# Back-end.net
KiCad netlist of a schematic drawn in Altium Designer
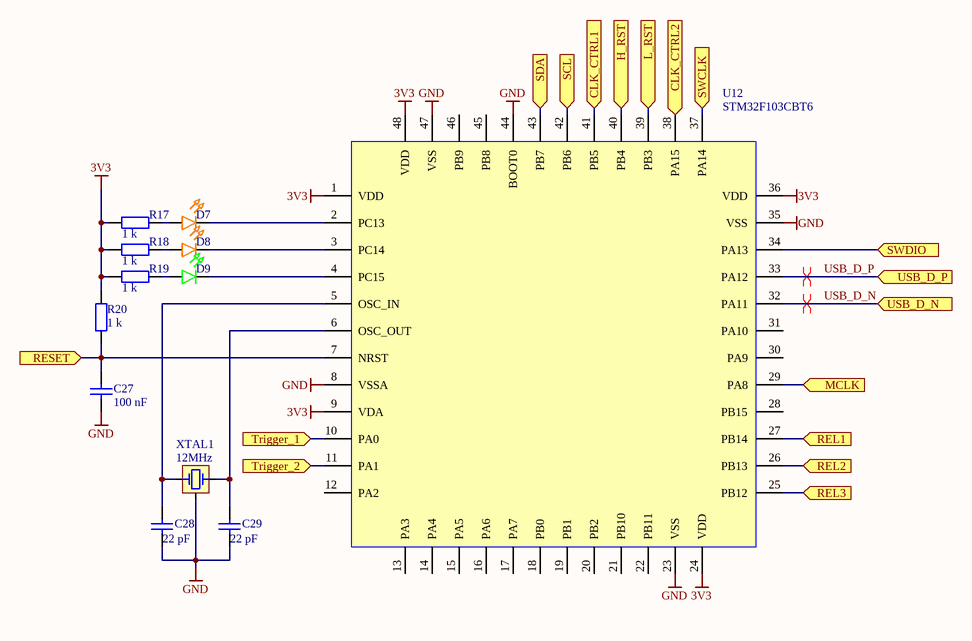
[diagram p0: Back-end.SchDoc]

(export (version "E")
  (design (tool "Eeschema 10.0.6"))
  (components
    (comp (ref "C27")
      (value "100 nF")
      (footprint "C1206")
      (description "Capacitor (Semiconductor SIM Model)")
      (fields (field (name "PUBLISHER") "Altium Limited"))
      (libsource (lib "Miscellaneous Devices") (part "Cap Semi"))
    )
    (comp (ref "C28")
      (value "22 pF")
      (footprint "C1206")
      (description "Capacitor (Semiconductor SIM Model)")
      (fields (field (name "PUBLISHER") "Altium Limited"))
      (libsource (lib "Miscellaneous Devices") (part "Cap Semi"))
    )
    (comp (ref "C29")
      (value "22 pF")
      (footprint "C1206")
      (description "Capacitor (Semiconductor SIM Model)")
      (fields (field (name "PUBLISHER") "Altium Limited"))
      (libsource (lib "Miscellaneous Devices") (part "Cap Semi"))
    )
    (comp (ref "D7")
      (value "LED Orange")
      (footprint "LED Diod red")
      (description "LED SMD Diod Orange")
      (libsource (lib "Diody") (part "LED SMD Diod Orange"))
    )
    (comp (ref "D8")
      (value "LED Orange")
      (footprint "LED Diod red")
      (description "LED SMD Diod Orange")
      (libsource (lib "Diody") (part "LED SMD Diod Orange"))
    )
    (comp (ref "D9")
      (value "*")
      (footprint "LED Diod grean")
      (libsource (lib "Diody") (part "LED SMD Diod Green"))
    )
    (comp (ref "R17")
      (value "1 k")
      (footprint "R1206")
      (description "Resistor")
      (fields (field (name "PUBLISHER") "Altium Limited"))
      (libsource (lib "Miscellaneous Devices") (part "Res2"))
    )
    (comp (ref "R18")
      (value "1 k")
      (footprint "R1206")
      (description "Resistor")
      (fields (field (name "PUBLISHER") "Altium Limited"))
      (libsource (lib "Miscellaneous Devices") (part "Res2"))
    )
    (comp (ref "R19")
      (value "1 k")
      (footprint "R1206")
      (description "Resistor")
      (fields (field (name "PUBLISHER") "Altium Limited"))
      (libsource (lib "Miscellaneous Devices") (part "Res2"))
    )
    (comp (ref "R20")
      (value "1 k")
      (footprint "R1206")
      (description "Resistor")
      (fields (field (name "PUBLISHER") "Altium Limited"))
      (libsource (lib "") (part "Res2_1"))
    )
    (comp (ref "U12")
      (value "STM32F103CBT6")
      (footprint "LQFP48_L")
      (libsource (lib "Schlib1") (part "STM32F070CxTxx"))
    )
    (comp (ref "XTAL1")
      (value "7M-12.000MAAJ-T")
      (footprint "XTAL 2.5MM X3.2MM")
      (description "TXC  7M-12.000MAAJ-T  CRYSTAL, 12MHZ, 18PF, 3.2 X 2.5MM")
      (fields (field (name "VALUE1") "12MHz"))
      (libsource (lib "Passive Components") (part "XTAL 12MHz"))
    )
  )
  (nets
    (net (code "1") (name "/CLK_CTRL1") (class "Default")
      (node (ref "U12") (pin "41") (pinfunction "PB5_41") (pintype "passive"))
    )
    (net (code "2") (name "/CLK_CTRL2") (class "Default")
      (node (ref "U12") (pin "38") (pinfunction "PA15_38") (pintype "passive"))
    )
    (net (code "3") (name "/H_RST") (class "Default")
      (node (ref "U12") (pin "40") (pinfunction "PB4_40") (pintype "passive"))
    )
    (net (code "4") (name "/L_RST") (class "Default")
      (node (ref "U12") (pin "39") (pinfunction "PB3_39") (pintype "passive"))
    )
    (net (code "5") (name "/MCLK") (class "Default")
      (node (ref "U12") (pin "29") (pinfunction "PA8_29") (pintype "passive"))
    )
    (net (code "6") (name "/REL1") (class "Default")
      (node (ref "U12") (pin "27") (pinfunction "PB14_27") (pintype "passive"))
    )
    (net (code "7") (name "/REL2") (class "Default")
      (node (ref "U12") (pin "26") (pinfunction "PB13_26") (pintype "passive"))
    )
    (net (code "8") (name "/REL3") (class "Default")
      (node (ref "U12") (pin "25") (pinfunction "PB12_25") (pintype "passive"))
    )
    (net (code "9") (name "/RESET") (class "Default")
      (node (ref "C27") (pin "2") (pinfunction "2_2") (pintype "passive"))
      (node (ref "R20") (pin "1") (pinfunction "1_1") (pintype "passive"))
      (node (ref "U12") (pin "7") (pinfunction "NRST_7") (pintype "passive"))
    )
    (net (code "10") (name "/SCL") (class "Default")
      (node (ref "U12") (pin "42") (pinfunction "PB6_42") (pintype "passive"))
    )
    (net (code "11") (name "/SDA") (class "Default")
      (node (ref "U12") (pin "43") (pinfunction "PB7_43") (pintype "passive"))
    )
    (net (code "12") (name "/SWCLK") (class "Default")
      (node (ref "U12") (pin "37") (pinfunction "PA14_37") (pintype "passive"))
    )
    (net (code "13") (name "/SWDIO") (class "Default")
      (node (ref "U12") (pin "34") (pinfunction "PA13_34") (pintype "passive"))
    )
    (net (code "14") (name "/Trigger_1") (class "Default")
      (node (ref "U12") (pin "10") (pinfunction "PA0_10") (pintype "passive"))
    )
    (net (code "15") (name "/Trigger_2") (class "Default")
      (node (ref "U12") (pin "11") (pinfunction "PA1_11") (pintype "passive"))
    )
    (net (code "16") (name "/USB_D_N") (class "Default")
      (node (ref "U12") (pin "32") (pinfunction "PA11_32") (pintype "passive"))
    )
    (net (code "17") (name "/USB_D_P") (class "Default")
      (node (ref "U12") (pin "33") (pinfunction "PA12_33") (pintype "passive"))
    )
    (net (code "18") (name "3V3") (class "Default")
      (node (ref "R17") (pin "2") (pinfunction "2_2") (pintype "passive"))
      (node (ref "R18") (pin "2") (pinfunction "2_2") (pintype "passive"))
      (node (ref "R19") (pin "2") (pinfunction "2_2") (pintype "passive"))
      (node (ref "R20") (pin "2") (pinfunction "2_2") (pintype "passive"))
      (node (ref "U12") (pin "1") (pinfunction "VDD_1") (pintype "passive"))
      (node (ref "U12") (pin "24") (pinfunction "VDD_24") (pintype "passive"))
      (node (ref "U12") (pin "36") (pinfunction "VDD_36") (pintype "passive"))
      (node (ref "U12") (pin "48") (pinfunction "VDD_48") (pintype "passive"))
      (node (ref "U12") (pin "9") (pinfunction "VDA_9") (pintype "passive"))
    )
    (net (code "19") (name "GND") (class "Default")
      (node (ref "C27") (pin "1") (pinfunction "1_1") (pintype "passive"))
      (node (ref "C28") (pin "2") (pinfunction "2_2") (pintype "passive"))
      (node (ref "C29") (pin "2") (pinfunction "2_2") (pintype "passive"))
      (node (ref "U12") (pin "23") (pinfunction "VSS_23") (pintype "passive"))
      (node (ref "U12") (pin "35") (pinfunction "VSS_35") (pintype "passive"))
      (node (ref "U12") (pin "44") (pinfunction "BOOT0_44") (pintype "passive"))
      (node (ref "U12") (pin "47") (pinfunction "VSS_47") (pintype "passive"))
      (node (ref "U12") (pin "8") (pinfunction "VSSA_8") (pintype "passive"))
      (node (ref "XTAL1") (pin "2") (pinfunction "2_2") (pintype "power_in"))
    )
    (net (code "20") (name "Net-(D7-Pad1)") (class "Default")
      (node (ref "D7") (pin "1") (pinfunction "1_1") (pintype "power_in"))
      (node (ref "R17") (pin "1") (pinfunction "1_1") (pintype "passive"))
    )
    (net (code "21") (name "Net-(D8-Pad1)") (class "Default")
      (node (ref "D8") (pin "1") (pinfunction "1_1") (pintype "power_in"))
      (node (ref "R18") (pin "1") (pinfunction "1_1") (pintype "passive"))
    )
    (net (code "22") (name "Net-(D9-Pad1)") (class "Default")
      (node (ref "D9") (pin "1") (pinfunction "1_1") (pintype "power_in"))
      (node (ref "R19") (pin "1") (pinfunction "1_1") (pintype "passive"))
    )
    (net (code "23") (name "Net-(U12-OSC_IN)") (class "Default")
      (node (ref "C28") (pin "1") (pinfunction "1_1") (pintype "passive"))
      (node (ref "U12") (pin "5") (pinfunction "OSC_IN_5") (pintype "passive"))
      (node (ref "XTAL1") (pin "1") (pinfunction "OSC1_1") (pintype "passive"))
    )
    (net (code "24") (name "Net-(U12-OSC_OUT)") (class "Default")
      (node (ref "C29") (pin "1") (pinfunction "1_1") (pintype "passive"))
      (node (ref "U12") (pin "6") (pinfunction "OSC_OUT_6") (pintype "passive"))
      (node (ref "XTAL1") (pin "3") (pinfunction "OSC2_3") (pintype "passive"))
    )
    (net (code "25") (name "Net-(U12-PC13)") (class "Default")
      (node (ref "D7") (pin "2") (pinfunction "2_2") (pintype "power_in"))
      (node (ref "U12") (pin "2") (pinfunction "PC13_2") (pintype "passive"))
    )
    (net (code "26") (name "Net-(U12-PC14)") (class "Default")
      (node (ref "D8") (pin "2") (pinfunction "2_2") (pintype "power_in"))
      (node (ref "U12") (pin "3") (pinfunction "PC14_3") (pintype "passive"))
    )
    (net (code "27") (name "Net-(U12-PC15)") (class "Default")
      (node (ref "D9") (pin "2") (pinfunction "2_2") (pintype "power_in"))
      (node (ref "U12") (pin "4") (pinfunction "PC15_4") (pintype "passive"))
    )
    (net (code "28") (name "unconnected-(U12-PA2-Pad12)") (class "Default")
      (node (ref "U12") (pin "12") (pinfunction "PA2_12") (pintype "passive"))
    )
    (net (code "29") (name "unconnected-(U12-PA3-Pad13)") (class "Default")
      (node (ref "U12") (pin "13") (pinfunction "PA3_13") (pintype "passive"))
    )
    (net (code "30") (name "unconnected-(U12-PA4-Pad14)") (class "Default")
      (node (ref "U12") (pin "14") (pinfunction "PA4_14") (pintype "passive"))
    )
    (net (code "31") (name "unconnected-(U12-PA5-Pad15)") (class "Default")
      (node (ref "U12") (pin "15") (pinfunction "PA5_15") (pintype "passive"))
    )
    (net (code "32") (name "unconnected-(U12-PA6-Pad16)") (class "Default")
      (node (ref "U12") (pin "16") (pinfunction "PA6_16") (pintype "passive"))
    )
    (net (code "33") (name "unconnected-(U12-PA7-Pad17)") (class "Default")
      (node (ref "U12") (pin "17") (pinfunction "PA7_17") (pintype "passive"))
    )
    (net (code "34") (name "unconnected-(U12-PA9-Pad30)") (class "Default")
      (node (ref "U12") (pin "30") (pinfunction "PA9_30") (pintype "passive"))
    )
    (net (code "35") (name "unconnected-(U12-PA10-Pad31)") (class "Default")
      (node (ref "U12") (pin "31") (pinfunction "PA10_31") (pintype "passive"))
    )
    (net (code "36") (name "unconnected-(U12-PB0-Pad18)") (class "Default")
      (node (ref "U12") (pin "18") (pinfunction "PB0_18") (pintype "passive"))
    )
    (net (code "37") (name "unconnected-(U12-PB1-Pad19)") (class "Default")
      (node (ref "U12") (pin "19") (pinfunction "PB1_19") (pintype "passive"))
    )
    (net (code "38") (name "unconnected-(U12-PB2-Pad20)") (class "Default")
      (node (ref "U12") (pin "20") (pinfunction "PB2_20") (pintype "passive"))
    )
    (net (code "39") (name "unconnected-(U12-PB8-Pad45)") (class "Default")
      (node (ref "U12") (pin "45") (pinfunction "PB8_45") (pintype "passive"))
    )
    (net (code "40") (name "unconnected-(U12-PB9-Pad46)") (class "Default")
      (node (ref "U12") (pin "46") (pinfunction "PB9_46") (pintype "passive"))
    )
    (net (code "41") (name "unconnected-(U12-PB10-Pad21)") (class "Default")
      (node (ref "U12") (pin "21") (pinfunction "PB10_21") (pintype "passive"))
    )
    (net (code "42") (name "unconnected-(U12-PB11-Pad22)") (class "Default")
      (node (ref "U12") (pin "22") (pinfunction "PB11_22") (pintype "passive"))
    )
    (net (code "43") (name "unconnected-(U12-PB15-Pad28)") (class "Default")
      (node (ref "U12") (pin "28") (pinfunction "PB15_28") (pintype "passive"))
    )
  )
)
